# Sheet.net
KiCad netlist of a schematic drawn in Altium Designer
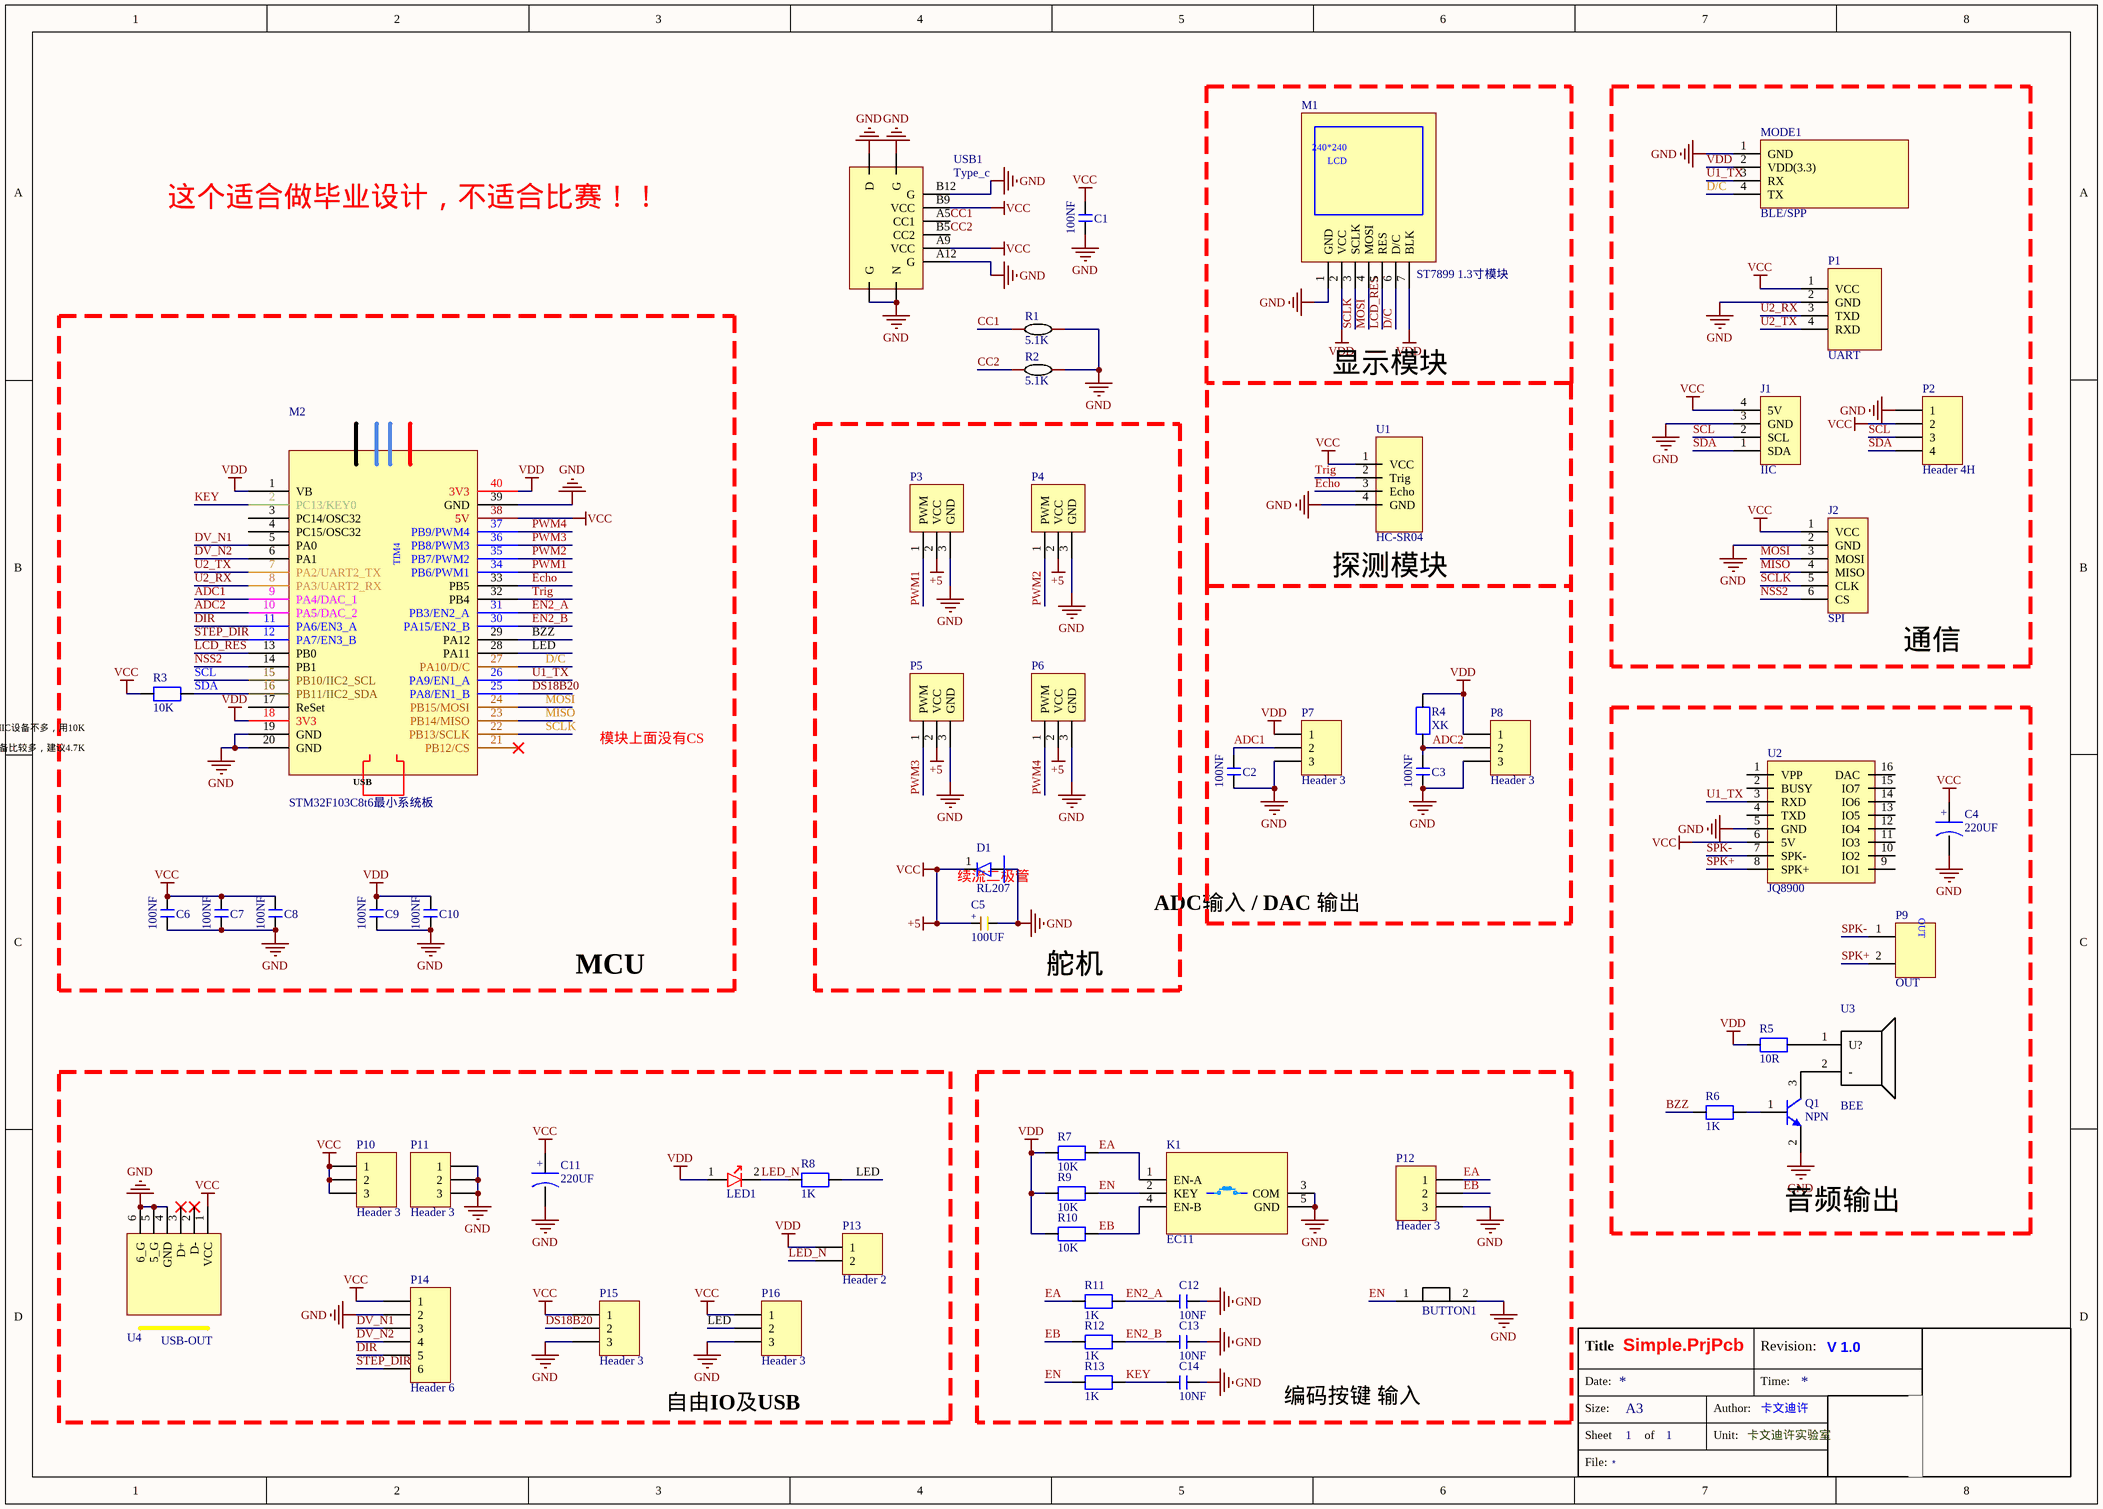
[diagram p0: Sheet.SchDoc]

(export (version "E")
  (design (tool "Eeschema 10.0.6"))
  (components
    (comp (ref "BUTTON1") (value "BUTTON") (footprint "KEY-A") (libsource (lib "Item_sch") (part "BUTTON")))
    (comp (ref "C1")
      (value "100NF")
      (footprint "CAP_0603")
      (description "CAP  12~50V")
      (libsource (lib "User") (part "CAP"))
    )
    (comp (ref "C2")
      (value "100NF")
      (footprint "CAP_0603")
      (description "CAP  12~50V")
      (libsource (lib "User") (part "CAP"))
    )
    (comp (ref "C3")
      (value "100NF")
      (footprint "CAP_0603")
      (description "CAP  12~50V")
      (libsource (lib "User") (part "CAP"))
    )
    (comp (ref "C4")
      (value "220UF")
      (footprint "CAP_PR_2.5_6.3_RA")
      (description "CAP 12V ~ 50V   电解电容")
      (libsource (lib "User") (part "CAP_BIG"))
    )
    (comp (ref "C5")
      (value "100UF")
      (footprint "CAP_3528_B")
      (description "CAP  6~12V  钽电容")
      (libsource (lib "Item_sch") (part "CAP_TA"))
    )
    (comp (ref "C6")
      (value "100NF")
      (footprint "CAP_0603")
      (description "CAP  12~50V")
      (libsource (lib "User") (part "CAP"))
    )
    (comp (ref "C7")
      (value "100NF")
      (footprint "CAP_0603")
      (description "CAP  12~50V")
      (libsource (lib "User") (part "CAP"))
    )
    (comp (ref "C8")
      (value "100NF")
      (footprint "CAP_0603")
      (description "CAP  12~50V")
      (libsource (lib "User") (part "CAP"))
    )
    (comp (ref "C9")
      (value "100NF")
      (footprint "CAP_0603")
      (description "CAP  12~50V")
      (libsource (lib "User") (part "CAP"))
    )
    (comp (ref "C10")
      (value "100NF")
      (footprint "CAP_0603")
      (description "CAP  12~50V")
      (libsource (lib "User") (part "CAP"))
    )
    (comp (ref "C11")
      (value "220UF")
      (footprint "CAP_PR_2.5_8")
      (description "CAP 12V ~ 50V   电解电容")
      (libsource (lib "User") (part "CAP_BIG"))
    )
    (comp (ref "C12")
      (value "10NF")
      (footprint "CAP_0603")
      (description "CAP  12~50V")
      (libsource (lib "User") (part "CAP"))
    )
    (comp (ref "C13")
      (value "10NF")
      (footprint "CAP_0603")
      (description "CAP  12~50V")
      (libsource (lib "User") (part "CAP"))
    )
    (comp (ref "C14")
      (value "10NF")
      (footprint "CAP_0603")
      (description "CAP  12~50V")
      (libsource (lib "User") (part "CAP"))
    )
    (comp (ref "D1")
      (value "RL207")
      (footprint "Diode_DO15")
      (description "Diode_肖特基/二极管 \r\n直插")
      (libsource (lib "User") (part "Diode-DO"))
    )
    (comp (ref "J1")
      (value "IIC")
      (footprint "XH2.54-WI-4P")
      (description "MLX90614 GY-906-BCC")
      (libsource (lib "Item_sch") (part "IIC"))
    )
    (comp (ref "J2")
      (value "SPI")
      (footprint "Header 2.54X6")
      (description "Heard")
      (libsource (lib "User") (part "SPI"))
    )
    (comp (ref "K1")
      (value "EC11")
      (footprint "EC-11")
      (description "KEY")
      (libsource (lib "User") (part "EN-CODE"))
    )
    (comp (ref "LED1")
      (value "LED_R/G/B/Y")
      (footprint "LED_5MM")
      (description "LED")
      (libsource (lib "Item_sch") (part "LED"))
    )
    (comp (ref "M1")
      (value "ST7899 1.3寸模块")
      (footprint "LCD-1.3_mode")
      (description "SHOW")
      (libsource (lib "Item_sch") (part "LCD_TFT_1.3_MODE"))
    )
    (comp (ref "M2")
      (value "STM32F103C8t6最小系统板")
      (footprint "STM32F103C8_mode")
      (libsource (lib "Item_sch") (part "STM32F103C8_mode"))
    )
    (comp (ref "MODE1")
      (value "BLE/SPP")
      (footprint "Header 2.54X4")
      (description "BLE4.2")
      (libsource (lib "Item_sch") (part "JDY-34"))
    )
    (comp (ref "P1")
      (value "UART")
      (footprint "XH2.54-WI-4P")
      (description "Header XH2.54 弯针座 4PIN")
      (libsource (lib "Item_sch") (part "UART"))
    )
    (comp (ref "P2")
      (value "Header 4H")
      (footprint "Header 2.54X4")
      (description "Header, 4-Pin, Right Angle")
      (fields (field (name "PUBLISHER") "Altium Limited"))
      (libsource (lib "Miscellaneous Connectors") (part "Header 4H"))
    )
    (comp (ref "P3")
      (value "Header3")
      (footprint "Header 2.54X3")
      (description "Header")
      (libsource (lib "Item_sch") (part "PWM_D"))
    )
    (comp (ref "P4")
      (value "Header3")
      (footprint "Header 2.54X3")
      (description "Header")
      (libsource (lib "Item_sch") (part "PWM_D"))
    )
    (comp (ref "P5")
      (value "Header3")
      (footprint "Header 2.54X3")
      (description "Header")
      (libsource (lib "Item_sch") (part "PWM_D"))
    )
    (comp (ref "P6")
      (value "Header3")
      (footprint "Header 2.54X3")
      (description "Header")
      (libsource (lib "Item_sch") (part "PWM_D"))
    )
    (comp (ref "P7")
      (value "Header 3")
      (footprint "Header 2.54X3")
      (description "Header, 3-Pin")
      (fields (field (name "PUBLISHER") "Altium Limited"))
      (libsource (lib "Miscellaneous Connectors") (part "Header 3"))
    )
    (comp (ref "P8")
      (value "Header 3")
      (footprint "Header 2.54X3")
      (description "Header, 3-Pin")
      (fields (field (name "PUBLISHER") "Altium Limited"))
      (libsource (lib "Miscellaneous Connectors") (part "Header 3"))
    )
    (comp (ref "P9")
      (value "OUT")
      (footprint "XH2.54-WI-2P")
      (description "Header")
      (libsource (lib "User") (part "OUT_2PIN"))
    )
    (comp (ref "P10")
      (value "Header 3")
      (footprint "Header 2.54X3")
      (description "Header, 3-Pin")
      (fields (field (name "PUBLISHER") "Altium Limited"))
      (libsource (lib "Miscellaneous Connectors") (part "Header 3"))
    )
    (comp (ref "P11")
      (value "Header 3")
      (footprint "Header 2.54X3")
      (description "Header, 3-Pin")
      (fields (field (name "PUBLISHER") "Altium Limited"))
      (libsource (lib "") (part "Header 3_1"))
    )
    (comp (ref "P12")
      (value "Header 3")
      (footprint "Header 2.54X3")
      (description "Header, 3-Pin")
      (fields (field (name "PUBLISHER") "Altium Limited"))
      (libsource (lib "") (part "Header 3_1"))
    )
    (comp (ref "P13")
      (value "Header 2")
      (footprint "HDR1X2")
      (description "Header, 2-Pin")
      (fields (field (name "PUBLISHER") "Altium Limited"))
      (libsource (lib "Miscellaneous Connectors") (part "Header 2"))
    )
    (comp (ref "P14")
      (value "Header 6")
      (footprint "HDR1X6")
      (description "Header, 6-Pin")
      (fields (field (name "PUBLISHER") "Altium Limited"))
      (libsource (lib "Miscellaneous Connectors") (part "Header 6"))
    )
    (comp (ref "P15")
      (value "Header 3")
      (footprint "XH2.54-WI-3P")
      (description "Header, 3-Pin")
      (fields (field (name "PUBLISHER") "Altium Limited"))
      (libsource (lib "Miscellaneous Connectors") (part "Header 3"))
    )
    (comp (ref "P16")
      (value "Header 3")
      (footprint "XH2.54-WI-3P")
      (description "Header, 3-Pin")
      (fields (field (name "PUBLISHER") "Altium Limited"))
      (libsource (lib "Miscellaneous Connectors") (part "Header 3"))
    )
    (comp (ref "Q1") (value "NPN") (footprint "SOT23_3") (libsource (lib "Item_sch") (part "Triode-NPN")))
    (comp (ref "R1") (value "5.1K") (footprint "RESC_0603_1") (libsource (lib "Item_sch") (part "RES")))
    (comp (ref "R2") (value "5.1K") (footprint "RESC_0603_1") (libsource (lib "Item_sch") (part "RES")))
    (comp (ref "R3")
      (value "10K")
      (footprint "RES_0.4_1/4W")
      (description "RES 贴片")
      (libsource (lib "User") (part "RES_S"))
    )
    (comp (ref "R4")
      (value "XK")
      (footprint "RES_0.4_1/4W")
      (description "RES 贴片")
      (libsource (lib "User") (part "RES_S"))
    )
    (comp (ref "R5")
      (value "10R")
      (footprint "RES_0.4_1/4W")
      (description "RES 贴片")
      (libsource (lib "User") (part "RES_S"))
    )
    (comp (ref "R6")
      (value "1K")
      (footprint "RES_0.4_1/4W")
      (description "RES 贴片")
      (libsource (lib "User") (part "RES_S"))
    )
    (comp (ref "R7")
      (value "10K")
      (footprint "RES_0.4_1/4W")
      (description "RES 贴片")
      (libsource (lib "User") (part "RES_S"))
    )
    (comp (ref "R8")
      (value "1K")
      (footprint "RES_0.4_1/4W")
      (description "RES 贴片")
      (libsource (lib "User") (part "RES_S"))
    )
    (comp (ref "R9")
      (value "10K")
      (footprint "RES_0.4_1/4W")
      (description "RES 贴片")
      (libsource (lib "User") (part "RES_S"))
    )
    (comp (ref "R10")
      (value "10K")
      (footprint "RES_0.4_1/4W")
      (description "RES 贴片")
      (libsource (lib "User") (part "RES_S"))
    )
    (comp (ref "R11")
      (value "1K")
      (footprint "RES_0.4_1/4W")
      (description "RES 贴片")
      (libsource (lib "User") (part "RES_S"))
    )
    (comp (ref "R12")
      (value "1K")
      (footprint "RES_0.4_1/4W")
      (description "RES 贴片")
      (libsource (lib "User") (part "RES_S"))
    )
    (comp (ref "R13")
      (value "1K")
      (footprint "RES_0.4_1/4W")
      (description "RES 贴片")
      (libsource (lib "User") (part "RES_S"))
    )
    (comp (ref "U1")
      (value "HC-SR04")
      (footprint "XH2.54-WI-4P")
      (description "Mode")
      (libsource (lib "Item_sch") (part "Ultrasonic"))
    )
    (comp (ref "U2")
      (value "JQ8900")
      (footprint "SpkMo")
      (description "MODE")
      (libsource (lib "User") (part "SPKMO_8900"))
    )
    (comp (ref "U3") (value "BEE") (footprint "BEE-FMQ5mm") (libsource (lib "User") (part "BZZ")))
    (comp (ref "U4")
      (value "USB-OUT")
      (footprint "USB_BA")
      (description "USB")
      (libsource (lib "Item_sch") (part "USB-OUT"))
    )
    (comp (ref "USB1")
      (value "Type_c")
      (footprint "USB-TYPE_6P")
      (description "USB")
      (libsource (lib "Item_sch") (part "USB-Type_c-6PIn"))
    )
  )
  (nets
    (net (code "1") (name "+5") (class "Default")
      (node (ref "C1") (pin "2") (pinfunction "0_2") (pintype "passive"))
      (node (ref "C11") (pin "1") (pinfunction "0_1") (pintype "passive"))
      (node (ref "C4") (pin "1") (pinfunction "0_1") (pintype "passive"))
      (node (ref "C5") (pin "1") (pinfunction "0_1") (pintype "passive"))
      (node (ref "C6") (pin "2") (pinfunction "0_2") (pintype "passive"))
      (node (ref "C7") (pin "2") (pinfunction "0_2") (pintype "passive"))
      (node (ref "C8") (pin "2") (pinfunction "0_2") (pintype "passive"))
      (node (ref "D1") (pin "1") (pinfunction "N_1") (pintype "passive"))
      (node (ref "J1") (pin "4") (pinfunction "5V_4") (pintype "passive"))
      (node (ref "J2") (pin "1") (pinfunction "VCC_1") (pintype "passive"))
      (node (ref "M2") (pin "38") (pinfunction "5V_38") (pintype "passive"))
      (node (ref "P1") (pin "1") (pinfunction "VCC_1") (pintype "passive"))
      (node (ref "P10") (pin "1") (pinfunction "1_1") (pintype "passive"))
      (node (ref "P10") (pin "2") (pinfunction "2_2") (pintype "passive"))
      (node (ref "P10") (pin "3") (pinfunction "3_3") (pintype "passive"))
      (node (ref "P14") (pin "1") (pinfunction "1_1") (pintype "passive"))
      (node (ref "P15") (pin "1") (pinfunction "1_1") (pintype "passive"))
      (node (ref "P16") (pin "1") (pinfunction "1_1") (pintype "passive"))
      (node (ref "P2") (pin "2") (pinfunction "2_2") (pintype "passive"))
      (node (ref "P3") (pin "2") (pinfunction "VCC_2") (pintype "passive"))
      (node (ref "P4") (pin "2") (pinfunction "VCC_2") (pintype "passive"))
      (node (ref "P5") (pin "2") (pinfunction "VCC_2") (pintype "passive"))
      (node (ref "P6") (pin "2") (pinfunction "VCC_2") (pintype "passive"))
      (node (ref "R3") (pin "1") (pinfunction "1_1") (pintype "passive"))
      (node (ref "U1") (pin "1") (pinfunction "VCC_1") (pintype "passive"))
      (node (ref "U2") (pin "6") (pinfunction "5V_6") (pintype "passive"))
      (node (ref "U4") (pin "1") (pinfunction "VCC_1") (pintype "passive"))
      (node (ref "USB1") (pin "A9") (pinfunction "VCC_A9") (pintype "passive"))
      (node (ref "USB1") (pin "B9") (pinfunction "VCC_B9") (pintype "passive"))
    )
    (net (code "2") (name "/ADC1") (class "Default")
      (node (ref "C2") (pin "2") (pinfunction "0_2") (pintype "passive"))
      (node (ref "M2") (pin "9") (pinfunction "PA4/DAC_1_9") (pintype "passive"))
      (node (ref "P7") (pin "2") (pinfunction "2_2") (pintype "passive"))
    )
    (net (code "3") (name "/ADC2") (class "Default")
      (node (ref "C3") (pin "2") (pinfunction "0_2") (pintype "passive"))
      (node (ref "M2") (pin "10") (pinfunction "PA5/DAC_2_10") (pintype "passive"))
      (node (ref "P8") (pin "2") (pinfunction "2_2") (pintype "passive"))
      (node (ref "R4") (pin "1") (pinfunction "1_1") (pintype "passive"))
    )
    (net (code "4") (name "/BZZ") (class "Default")
      (node (ref "M2") (pin "29") (pinfunction "PA12_29") (pintype "passive"))
      (node (ref "R6") (pin "1") (pinfunction "1_1") (pintype "passive"))
    )
    (net (code "5") (name "/CC1") (class "Default")
      (node (ref "R1") (pin "1") (pinfunction "1_1") (pintype "passive"))
      (node (ref "USB1") (pin "A5") (pinfunction "CC1_A5") (pintype "passive"))
    )
    (net (code "6") (name "/CC2") (class "Default")
      (node (ref "R2") (pin "1") (pinfunction "1_1") (pintype "passive"))
      (node (ref "USB1") (pin "B5") (pinfunction "CC2_B5") (pintype "passive"))
    )
    (net (code "7") (name "/DIR") (class "Default")
      (node (ref "M2") (pin "11") (pinfunction "PA6/EN3_A_11") (pintype "passive"))
      (node (ref "P14") (pin "5") (pinfunction "5_5") (pintype "passive"))
    )
    (net (code "8") (name "/DS18B20") (class "Default")
      (node (ref "M2") (pin "25") (pinfunction "PA8/EN1_B_25") (pintype "passive"))
      (node (ref "P15") (pin "2") (pinfunction "2_2") (pintype "passive"))
    )
    (net (code "9") (name "/DV_N1") (class "Default")
      (node (ref "M2") (pin "5") (pinfunction "PA0_5") (pintype "passive"))
      (node (ref "P14") (pin "3") (pinfunction "3_3") (pintype "passive"))
    )
    (net (code "10") (name "/DV_N2") (class "Default")
      (node (ref "M2") (pin "6") (pinfunction "PA1_6") (pintype "passive"))
      (node (ref "P14") (pin "4") (pinfunction "4_4") (pintype "passive"))
    )
    (net (code "11") (name "/D{slash}C") (class "Default")
      (node (ref "M1") (pin "6") (pinfunction "D/C_6") (pintype "passive"))
      (node (ref "M2") (pin "27") (pinfunction "PA10/D/C_27") (pintype "passive"))
      (node (ref "MODE1") (pin "4") (pinfunction "TX_4") (pintype "passive"))
    )
    (net (code "12") (name "/EA") (class "Default")
      (node (ref "K1") (pin "1") (pinfunction "EN-A_1") (pintype "passive"))
      (node (ref "P12") (pin "1") (pinfunction "1_1") (pintype "passive"))
      (node (ref "R11") (pin "1") (pinfunction "1_1") (pintype "passive"))
      (node (ref "R7") (pin "2") (pinfunction "2_2") (pintype "passive"))
    )
    (net (code "13") (name "/EB") (class "Default")
      (node (ref "K1") (pin "4") (pinfunction "EN-B_4") (pintype "passive"))
      (node (ref "P12") (pin "2") (pinfunction "2_2") (pintype "passive"))
      (node (ref "R10") (pin "2") (pinfunction "2_2") (pintype "passive"))
      (node (ref "R12") (pin "1") (pinfunction "1_1") (pintype "passive"))
    )
    (net (code "14") (name "/EN") (class "Default")
      (node (ref "BUTTON1") (pin "1") (pinfunction "1_1") (pintype "passive"))
      (node (ref "K1") (pin "2") (pinfunction "KEY_2") (pintype "passive"))
      (node (ref "R13") (pin "1") (pinfunction "1_1") (pintype "passive"))
      (node (ref "R9") (pin "2") (pinfunction "2_2") (pintype "passive"))
    )
    (net (code "15") (name "/EN2_A") (class "Default")
      (node (ref "C12") (pin "2") (pinfunction "0_2") (pintype "passive"))
      (node (ref "M2") (pin "31") (pinfunction "PB3/EN2_A_31") (pintype "passive"))
      (node (ref "R11") (pin "2") (pinfunction "2_2") (pintype "passive"))
    )
    (net (code "16") (name "/EN2_B") (class "Default")
      (node (ref "C13") (pin "2") (pinfunction "0_2") (pintype "passive"))
      (node (ref "M2") (pin "30") (pinfunction "PA15/EN2_B_30") (pintype "passive"))
      (node (ref "R12") (pin "2") (pinfunction "2_2") (pintype "passive"))
    )
    (net (code "17") (name "/Echo") (class "Default")
      (node (ref "M2") (pin "33") (pinfunction "PB5_33") (pintype "passive"))
      (node (ref "U1") (pin "3") (pinfunction "Echo_3") (pintype "passive"))
    )
    (net (code "18") (name "/KEY") (class "Default")
      (node (ref "C14") (pin "2") (pinfunction "0_2") (pintype "passive"))
      (node (ref "M2") (pin "2") (pinfunction "PC13/KEY0_2") (pintype "passive"))
      (node (ref "R13") (pin "2") (pinfunction "2_2") (pintype "passive"))
    )
    (net (code "19") (name "/LCD_RES") (class "Default")
      (node (ref "M1") (pin "5") (pinfunction "RES_5") (pintype "passive"))
      (node (ref "M2") (pin "13") (pinfunction "PB0_13") (pintype "passive"))
    )
    (net (code "20") (name "/LED") (class "Default")
      (node (ref "M2") (pin "28") (pinfunction "PA11_28") (pintype "passive"))
      (node (ref "P16") (pin "2") (pinfunction "2_2") (pintype "passive"))
      (node (ref "R8") (pin "2") (pinfunction "2_2") (pintype "passive"))
    )
    (net (code "21") (name "/LED_N") (class "Default")
      (node (ref "LED1") (pin "2") (pinfunction "-_2") (pintype "passive"))
      (node (ref "P13") (pin "2") (pinfunction "2_2") (pintype "passive"))
      (node (ref "R8") (pin "1") (pinfunction "1_1") (pintype "passive"))
    )
    (net (code "22") (name "/MISO") (class "Default")
      (node (ref "J2") (pin "4") (pinfunction "MISO_4") (pintype "passive"))
      (node (ref "M2") (pin "23") (pinfunction "PB14/MISO_23") (pintype "passive"))
    )
    (net (code "23") (name "/MOSI") (class "Default")
      (node (ref "J2") (pin "3") (pinfunction "MOSI_3") (pintype "passive"))
      (node (ref "M1") (pin "4") (pinfunction "MOSI_4") (pintype "passive"))
      (node (ref "M2") (pin "24") (pinfunction "PB15/MOSI_24") (pintype "passive"))
    )
    (net (code "24") (name "/NSS2") (class "Default")
      (node (ref "J2") (pin "6") (pinfunction "CS_6") (pintype "passive"))
      (node (ref "M2") (pin "14") (pinfunction "PB1_14") (pintype "passive"))
    )
    (net (code "25") (name "/PWM1") (class "Default")
      (node (ref "M2") (pin "34") (pinfunction "PB6/PWM1_34") (pintype "passive"))
      (node (ref "P3") (pin "1") (pinfunction "PWM_1") (pintype "passive"))
    )
    (net (code "26") (name "/PWM2") (class "Default")
      (node (ref "M2") (pin "35") (pinfunction "PB7/PWM2_35") (pintype "passive"))
      (node (ref "P4") (pin "1") (pinfunction "PWM_1") (pintype "passive"))
    )
    (net (code "27") (name "/PWM3") (class "Default")
      (node (ref "M2") (pin "36") (pinfunction "PB8/PWM3_36") (pintype "passive"))
      (node (ref "P5") (pin "1") (pinfunction "PWM_1") (pintype "passive"))
    )
    (net (code "28") (name "/PWM4") (class "Default")
      (node (ref "M2") (pin "37") (pinfunction "PB9/PWM4_37") (pintype "passive"))
      (node (ref "P6") (pin "1") (pinfunction "PWM_1") (pintype "passive"))
    )
    (net (code "29") (name "/SCL") (class "Default")
      (node (ref "J1") (pin "2") (pinfunction "SCL_2") (pintype "passive"))
      (node (ref "M2") (pin "15") (pinfunction "PB10/IIC2_SCL_15") (pintype "passive"))
      (node (ref "P2") (pin "3") (pinfunction "3_3") (pintype "passive"))
    )
    (net (code "30") (name "/SCLK") (class "Default")
      (node (ref "J2") (pin "5") (pinfunction "CLK_5") (pintype "passive"))
      (node (ref "M1") (pin "3") (pinfunction "SCLK_3") (pintype "passive"))
      (node (ref "M2") (pin "22") (pinfunction "PB13/SCLK_22") (pintype "passive"))
    )
    (net (code "31") (name "/SDA") (class "Default")
      (node (ref "J1") (pin "1") (pinfunction "SDA_1") (pintype "passive"))
      (node (ref "M2") (pin "16") (pinfunction "PB11/IIC2_SDA_16") (pintype "passive"))
      (node (ref "P2") (pin "4") (pinfunction "4_4") (pintype "passive"))
      (node (ref "R3") (pin "2") (pinfunction "2_2") (pintype "passive"))
    )
    (net (code "32") (name "/SPK+") (class "Default")
      (node (ref "P9") (pin "2") (pintype "passive"))
      (node (ref "U2") (pin "8") (pinfunction "SPK+_8") (pintype "passive"))
    )
    (net (code "33") (name "/SPK-") (class "Default")
      (node (ref "P9") (pin "1") (pintype "passive"))
      (node (ref "U2") (pin "7") (pinfunction "SPK-_7") (pintype "passive"))
    )
    (net (code "34") (name "/STEP_DIR") (class "Default")
      (node (ref "M2") (pin "12") (pinfunction "PA7/EN3_B_12") (pintype "passive"))
      (node (ref "P14") (pin "6") (pinfunction "6_6") (pintype "passive"))
    )
    (net (code "35") (name "/Trig") (class "Default")
      (node (ref "M2") (pin "32") (pinfunction "PB4_32") (pintype "passive"))
      (node (ref "U1") (pin "2") (pinfunction "Trig_2") (pintype "passive"))
    )
    (net (code "36") (name "/U1_TX") (class "Default")
      (node (ref "M2") (pin "26") (pinfunction "PA9/EN1_A_26") (pintype "passive"))
      (node (ref "MODE1") (pin "3") (pinfunction "RX_3") (pintype "passive"))
      (node (ref "U2") (pin "3") (pinfunction "RXD_3") (pintype "passive"))
    )
    (net (code "37") (name "/U2_RX") (class "Default")
      (node (ref "M2") (pin "8") (pinfunction "PA3/UART2_RX_8") (pintype "passive"))
      (node (ref "P1") (pin "3") (pinfunction "TXD_3") (pintype "passive"))
    )
    (net (code "38") (name "/U2_TX") (class "Default")
      (node (ref "M2") (pin "7") (pinfunction "PA2/UART2_TX_7") (pintype "passive"))
      (node (ref "P1") (pin "4") (pinfunction "RXD_4") (pintype "passive"))
    )
    (net (code "39") (name "GND") (class "Default")
      (node (ref "BUTTON1") (pin "2") (pinfunction "2_2") (pintype "passive"))
      (node (ref "C1") (pin "1") (pinfunction "0_1") (pintype "passive"))
      (node (ref "C10") (pin "1") (pinfunction "0_1") (pintype "passive"))
      (node (ref "C11") (pin "2") (pinfunction "0_2") (pintype "passive"))
      (node (ref "C12") (pin "1") (pinfunction "0_1") (pintype "passive"))
      (node (ref "C13") (pin "1") (pinfunction "0_1") (pintype "passive"))
      (node (ref "C14") (pin "1") (pinfunction "0_1") (pintype "passive"))
      (node (ref "C2") (pin "1") (pinfunction "0_1") (pintype "passive"))
      (node (ref "C3") (pin "1") (pinfunction "0_1") (pintype "passive"))
      (node (ref "C4") (pin "2") (pinfunction "0_2") (pintype "passive"))
      (node (ref "C5") (pin "2") (pinfunction "0_2") (pintype "passive"))
      (node (ref "C6") (pin "1") (pinfunction "0_1") (pintype "passive"))
      (node (ref "C7") (pin "1") (pinfunction "0_1") (pintype "passive"))
      (node (ref "C8") (pin "1") (pinfunction "0_1") (pintype "passive"))
      (node (ref "C9") (pin "1") (pinfunction "0_1") (pintype "passive"))
      (node (ref "D1") (pin "2") (pinfunction "P_2") (pintype "passive"))
      (node (ref "J1") (pin "3") (pinfunction "GND_3") (pintype "passive"))
      (node (ref "J2") (pin "2") (pinfunction "GND_2") (pintype "passive"))
      (node (ref "K1") (pin "3") (pinfunction "COM_3") (pintype "passive"))
      (node (ref "K1") (pin "5") (pinfunction "GND_5") (pintype "passive"))
      (node (ref "M1") (pin "1") (pinfunction "GND_1") (pintype "passive"))
      (node (ref "M2") (pin "19") (pinfunction "GND_19") (pintype "passive"))
      (node (ref "M2") (pin "20") (pinfunction "GND_20") (pintype "passive"))
      (node (ref "M2") (pin "39") (pinfunction "GND_39") (pintype "passive"))
      (node (ref "MODE1") (pin "1") (pinfunction "GND_1") (pintype "passive"))
      (node (ref "P1") (pin "2") (pinfunction "GND_2") (pintype "passive"))
      (node (ref "P11") (pin "1") (pinfunction "1_1") (pintype "passive"))
      (node (ref "P11") (pin "2") (pinfunction "2_2") (pintype "passive"))
      (node (ref "P11") (pin "3") (pinfunction "3_3") (pintype "passive"))
      (node (ref "P12") (pin "3") (pinfunction "3_3") (pintype "passive"))
      (node (ref "P14") (pin "2") (pinfunction "2_2") (pintype "passive"))
      (node (ref "P15") (pin "3") (pinfunction "3_3") (pintype "passive"))
      (node (ref "P16") (pin "3") (pinfunction "3_3") (pintype "passive"))
      (node (ref "P2") (pin "1") (pinfunction "1_1") (pintype "passive"))
      (node (ref "P3") (pin "3") (pinfunction "GND_3") (pintype "passive"))
      (node (ref "P4") (pin "3") (pinfunction "GND_3") (pintype "passive"))
      (node (ref "P5") (pin "3") (pinfunction "GND_3") (pintype "passive"))
      (node (ref "P6") (pin "3") (pinfunction "GND_3") (pintype "passive"))
      (node (ref "P7") (pin "3") (pinfunction "3_3") (pintype "passive"))
      (node (ref "P8") (pin "3") (pinfunction "3_3") (pintype "passive"))
      (node (ref "Q1") (pin "2") (pinfunction "E_2") (pintype "passive"))
      (node (ref "R1") (pin "2") (pinfunction "2_2") (pintype "passive"))
      (node (ref "R2") (pin "2") (pinfunction "2_2") (pintype "passive"))
      (node (ref "U1") (pin "4") (pinfunction "GND_4") (pintype "passive"))
      (node (ref "U2") (pin "5") (pinfunction "GND_5") (pintype "passive"))
      (node (ref "U4") (pin "4") (pinfunction "GND_4") (pintype "passive"))
      (node (ref "U4") (pin "5") (pinfunction "5_G_5") (pintype "passive"))
      (node (ref "U4") (pin "6") (pinfunction "6_G_6") (pintype "passive"))
      (node (ref "USB1") (pin "A") (pinfunction "G_A") (pintype "passive"))
      (node (ref "USB1") (pin "A12") (pinfunction "G_A12") (pintype "passive"))
      (node (ref "USB1") (pin "B") (pinfunction "N_B") (pintype "passive"))
      (node (ref "USB1") (pin "B12") (pinfunction "G_B12") (pintype "passive"))
      (node (ref "USB1") (pin "C") (pinfunction "D_C") (pintype "passive"))
      (node (ref "USB1") (pin "D") (pinfunction "G_D") (pintype "passive"))
    )
    (net (code "40") (name "Net-(Q1-B)") (class "Default")
      (node (ref "Q1") (pin "1") (pinfunction "B_1") (pintype "passive"))
      (node (ref "R6") (pin "2") (pinfunction "2_2") (pintype "passive"))
    )
    (net (code "41") (name "Net-(Q1-C)") (class "Default")
      (node (ref "Q1") (pin "3") (pinfunction "C_3") (pintype "passive"))
      (node (ref "U3") (pin "2") (pinfunction "-_2") (pintype "passive"))
    )
    (net (code "42") (name "Net-(U3-U?)") (class "Default")
      (node (ref "R5") (pin "2") (pinfunction "2_2") (pintype "passive"))
      (node (ref "U3") (pin "1") (pinfunction "U?_1") (pintype "passive"))
    )
    (net (code "43") (name "VDD") (class "Default")
      (node (ref "C10") (pin "2") (pinfunction "0_2") (pintype "passive"))
      (node (ref "C9") (pin "2") (pinfunction "0_2") (pintype "passive"))
      (node (ref "LED1") (pin "1") (pinfunction "+_1") (pintype "passive"))
      (node (ref "M1") (pin "2") (pinfunction "VCC_2") (pintype "passive"))
      (node (ref "M1") (pin "7") (pinfunction "BLK_7") (pintype "passive"))
      (node (ref "M2") (pin "1") (pinfunction "VB_1") (pintype "passive"))
      (node (ref "M2") (pin "18") (pinfunction "3V3_18") (pintype "passive"))
      (node (ref "M2") (pin "40") (pinfunction "3V3_40") (pintype "passive"))
      (node (ref "MODE1") (pin "2") (pinfunction "VDD(3.3)_2") (pintype "passive"))
      (node (ref "P13") (pin "1") (pinfunction "1_1") (pintype "passive"))
      (node (ref "P7") (pin "1") (pinfunction "1_1") (pintype "passive"))
      (node (ref "P8") (pin "1") (pinfunction "1_1") (pintype "passive"))
      (node (ref "R10") (pin "1") (pinfunction "1_1") (pintype "passive"))
      (node (ref "R4") (pin "2") (pinfunction "2_2") (pintype "passive"))
      (node (ref "R5") (pin "1") (pinfunction "1_1") (pintype "passive"))
      (node (ref "R7") (pin "1") (pinfunction "1_1") (pintype "passive"))
      (node (ref "R9") (pin "1") (pinfunction "1_1") (pintype "passive"))
    )
    (net (code "44") (name "unconnected-(M2-PB12{slash}CS-Pad21)") (class "Default")
      (node (ref "M2") (pin "21") (pinfunction "PB12/CS_21") (pintype "passive+no_connect"))
    )
    (net (code "45") (name "unconnected-(M2-PC14{slash}OSC32-Pad3)") (class "Default")
      (node (ref "M2") (pin "3") (pinfunction "PC14/OSC32_3") (pintype "passive"))
    )
    (net (code "46") (name "unconnected-(M2-PC15{slash}OSC32-Pad4)") (class "Default")
      (node (ref "M2") (pin "4") (pinfunction "PC15/OSC32_4") (pintype "passive"))
    )
    (net (code "47") (name "unconnected-(M2-ReSet-Pad17)") (class "Default")
      (node (ref "M2") (pin "17") (pinfunction "ReSet_17") (pintype "passive"))
    )
    (net (code "48") (name "unconnected-(U2-BUSY-Pad2)") (class "Default")
      (node (ref "U2") (pin "2") (pinfunction "BUSY_2") (pintype "passive"))
    )
    (net (code "49") (name "unconnected-(U2-DAC-Pad16)") (class "Default")
      (node (ref "U2") (pin "16") (pinfunction "DAC_16") (pintype "passive"))
    )
    (net (code "50") (name "unconnected-(U2-IO1-Pad9)") (class "Default")
      (node (ref "U2") (pin "9") (pinfunction "IO1_9") (pintype "passive"))
    )
    (net (code "51") (name "unconnected-(U2-IO2-Pad10)") (class "Default")
      (node (ref "U2") (pin "10") (pinfunction "IO2_10") (pintype "passive"))
    )
    (net (code "52") (name "unconnected-(U2-IO3-Pad11)") (class "Default")
      (node (ref "U2") (pin "11") (pinfunction "IO3_11") (pintype "passive"))
    )
    (net (code "53") (name "unconnected-(U2-IO4-Pad12)") (class "Default")
      (node (ref "U2") (pin "12") (pinfunction "IO4_12") (pintype "passive"))
    )
    (net (code "54") (name "unconnected-(U2-IO5-Pad13)") (class "Default")
      (node (ref "U2") (pin "13") (pinfunction "IO5_13") (pintype "passive"))
    )
    (net (code "55") (name "unconnected-(U2-IO6-Pad14)") (class "Default")
      (node (ref "U2") (pin "14") (pinfunction "IO6_14") (pintype "passive"))
    )
    (net (code "56") (name "unconnected-(U2-IO7-Pad15)") (class "Default")
      (node (ref "U2") (pin "15") (pinfunction "IO7_15") (pintype "passive"))
    )
    (net (code "57") (name "unconnected-(U2-TXD-Pad4)") (class "Default")
      (node (ref "U2") (pin "4") (pinfunction "TXD_4") (pintype "passive"))
    )
    (net (code "58") (name "unconnected-(U2-VPP-Pad1)") (class "Default")
      (node (ref "U2") (pin "1") (pinfunction "VPP_1") (pintype "passive"))
    )
    (net (code "59") (name "unconnected-(U4-D+-Pad3)") (class "Default")
      (node (ref "U4") (pin "3") (pinfunction "D+_3") (pintype "passive+no_connect"))
    )
    (net (code "60") (name "unconnected-(U4-D--Pad2)") (class "Default")
      (node (ref "U4") (pin "2") (pinfunction "D-_2") (pintype "passive+no_connect"))
    )
  )
)
